# Power_Supply_Noise_Canceller.net
KiCad netlist of a schematic drawn in Altium Designer
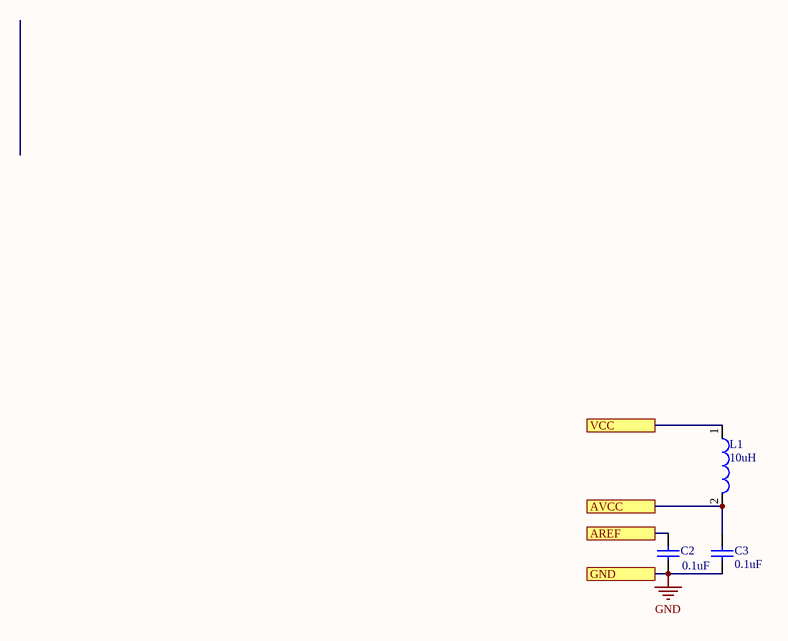
[diagram p0: Power Supply Noise Canceller.SchDoc]

(export (version "E")
  (design (tool "Eeschema 10.0.6"))
  (components
    (comp (ref "C2")
      (value "0.1uF")
      (footprint "CAPC2013X94X50LL20T25")
      (description "Chip Capacitor, 0.1 uF, +/- 5%, 50 V, -55 to 125 degC, 0805 (2012 Metric), RoHS, Tape and Reel")
      (fields (field (name "TOLERANCE") "5%") (field (name "MANUFACTURER") "AVX"))
      (libsource (lib "Altium Content Vault") (part "CAP-NP-2"))
    )
    (comp (ref "C3")
      (value "0.1uF")
      (footprint "CAPC2013X94X50LL20T25")
      (description "Chip Capacitor, 0.1 uF, +/- 5%, 50 V, -55 to 125 degC, 0805 (2012 Metric), RoHS, Tape and Reel")
      (fields (field (name "TOLERANCE") "5%") (field (name "MANUFACTURER") "AVX"))
      (libsource (lib "Altium Content Vault") (part "CAP-NP-2"))
    )
    (comp (ref "L1")
      (value "10uH")
      (footprint "SMD 0805_A")
      (description "Power Multilayer Inductor WE-PMI, L=10.0 µH")
      (fields (field (name "PARTNUMBER") "74479777310") (field (name "MANUFACTURER") "Wuerth Elektronik"))
      (libsource (lib "Altium Content Vault") (part "PAS-IND-INDUCTOR-2"))
    )
  )
  (nets
    (net (code "1") (name "/AREF") (class "Default")
      (node (ref "C2") (pin "2") (pinfunction "2_2") (pintype "passive"))
    )
    (net (code "2") (name "/AVCC") (class "Default")
      (node (ref "C3") (pin "2") (pinfunction "2_2") (pintype "passive"))
      (node (ref "L1") (pin "2") (pinfunction "2_2") (pintype "passive"))
    )
    (net (code "3") (name "/VCC") (class "Default")
      (node (ref "L1") (pin "1") (pinfunction "1_1") (pintype "passive"))
    )
    (net (code "4") (name "GND") (class "Default")
      (node (ref "C2") (pin "1") (pinfunction "1_1") (pintype "passive"))
      (node (ref "C3") (pin "1") (pinfunction "1_1") (pintype "passive"))
    )
  )
)
